# fonte.net
KiCad netlist of a schematic drawn in EAGLE
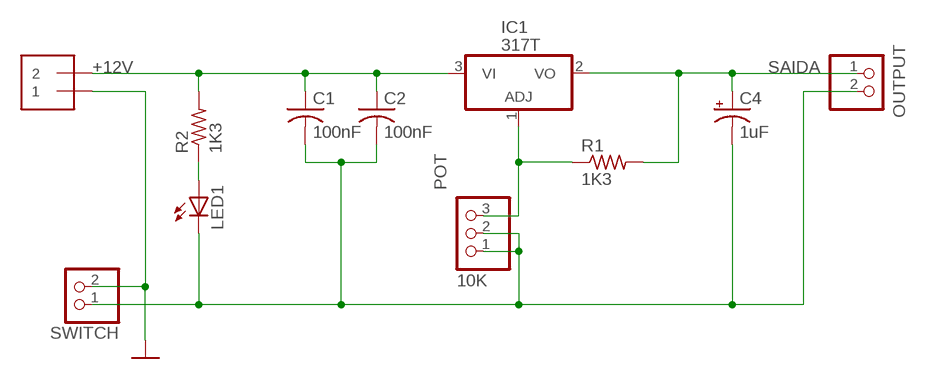
[diagram p0: schematic, sheet 1]

(export (version "E")
  (design (tool "Eeschema 10.0.6"))
  (components
    (comp (ref "C1")
      (value "100nF")
      (footprint "eagle-import:C025-025X050")
      (libsource (lib "eagle-import") (part "C-US025-025X050"))
    )
    (comp (ref "C2")
      (value "100nF")
      (footprint "eagle-import:C025-025X050")
      (libsource (lib "eagle-import") (part "C-US025-025X050"))
    )
    (comp (ref "C4")
      (value "1uF")
      (footprint "eagle-import:CPOL-RADIAL-2.5MM-5MM")
      (libsource (lib "eagle-import") (part "10UF-POLAR-RADIAL-2.5MM-25V-20%"))
    )
    (comp (ref "IC1")
      (value "317T")
      (footprint "eagle-import:TO220H")
      (libsource (lib "eagle-import") (part "317T"))
    )
    (comp (ref "INPUT")
      (value "1X2-3.5MM")
      (footprint "eagle-import:1X2-3.5MM")
      (libsource (lib "eagle-import") (part "1X2-3.5MM"))
    )
    (comp (ref "LED1")
      (value "LED5MM")
      (footprint "eagle-import:LED5MM")
      (libsource (lib "eagle-import") (part "LED5MM"))
    )
    (comp (ref "OUTPUT")
      (value "PINHD-1X2")
      (footprint "eagle-import:1X02")
      (libsource (lib "eagle-import") (part "PINHD-1X2"))
    )
    (comp (ref "POT")
      (value "10K")
      (footprint "eagle-import:1X03")
      (libsource (lib "eagle-import") (part "PINHD-1X3"))
    )
    (comp (ref "R1")
      (value "1K3")
      (footprint "eagle-import:0204_7")
      (libsource (lib "eagle-import") (part "R-US_0204/7"))
    )
    (comp (ref "R2")
      (value "1K3")
      (footprint "eagle-import:0204_7")
      (libsource (lib "eagle-import") (part "R-US_0204/7"))
    )
    (comp (ref "SWITCH")
      (value "PINHD-1X2")
      (footprint "eagle-import:1X02")
      (libsource (lib "eagle-import") (part "PINHD-1X2"))
    )
  )
  (nets
    (net (code "1") (name "/+12V") (class "Default")
      (node (ref "C1") (pin "1") (pinfunction "1_1") (pintype "passive"))
      (node (ref "C2") (pin "1") (pinfunction "1_1") (pintype "passive"))
      (node (ref "IC1") (pin "3") (pinfunction "VI_3") (pintype "input"))
      (node (ref "INPUT") (pin "2") (pinfunction "2_2") (pintype "passive"))
      (node (ref "R2") (pin "2") (pinfunction "2_2") (pintype "passive"))
    )
    (net (code "2") (name "/SAIDA") (class "Default")
      (node (ref "C4") (pin "1") (pinfunction "+_1") (pintype "passive"))
      (node (ref "IC1") (pin "2") (pinfunction "VO_2") (pintype "passive"))
      (node (ref "OUTPUT") (pin "1") (pinfunction "1_1") (pintype "passive"))
      (node (ref "R1") (pin "2") (pinfunction "2_2") (pintype "passive"))
    )
    (net (code "3") (name "GND") (class "Default")
      (node (ref "INPUT") (pin "1") (pinfunction "1_1") (pintype "passive"))
      (node (ref "SWITCH") (pin "2") (pinfunction "2_2") (pintype "passive"))
    )
    (net (code "4") (name "Net-(C4--)") (class "Default")
      (node (ref "C1") (pin "2") (pinfunction "2_2") (pintype "passive"))
      (node (ref "C2") (pin "2") (pinfunction "2_2") (pintype "passive"))
      (node (ref "C4") (pin "2") (pinfunction "-_2") (pintype "passive"))
      (node (ref "LED1") (pin "K") (pinfunction "C_K") (pintype "passive"))
      (node (ref "OUTPUT") (pin "2") (pinfunction "2_2") (pintype "passive"))
      (node (ref "POT") (pin "1") (pinfunction "1_1") (pintype "passive"))
      (node (ref "POT") (pin "2") (pinfunction "2_2") (pintype "passive"))
      (node (ref "SWITCH") (pin "1") (pinfunction "1_1") (pintype "passive"))
    )
    (net (code "5") (name "Net-(IC1-ADJ)") (class "Default")
      (node (ref "IC1") (pin "1") (pinfunction "ADJ_1") (pintype "input"))
      (node (ref "POT") (pin "3") (pinfunction "3_3") (pintype "passive"))
      (node (ref "R1") (pin "1") (pinfunction "1_1") (pintype "passive"))
    )
    (net (code "6") (name "Net-(LED1-PadA)") (class "Default")
      (node (ref "LED1") (pin "A") (pinfunction "A_A") (pintype "passive"))
      (node (ref "R2") (pin "1") (pinfunction "1_1") (pintype "passive"))
    )
  )
)
